# LED_driver.net
KiCad netlist of a schematic drawn in EAGLE
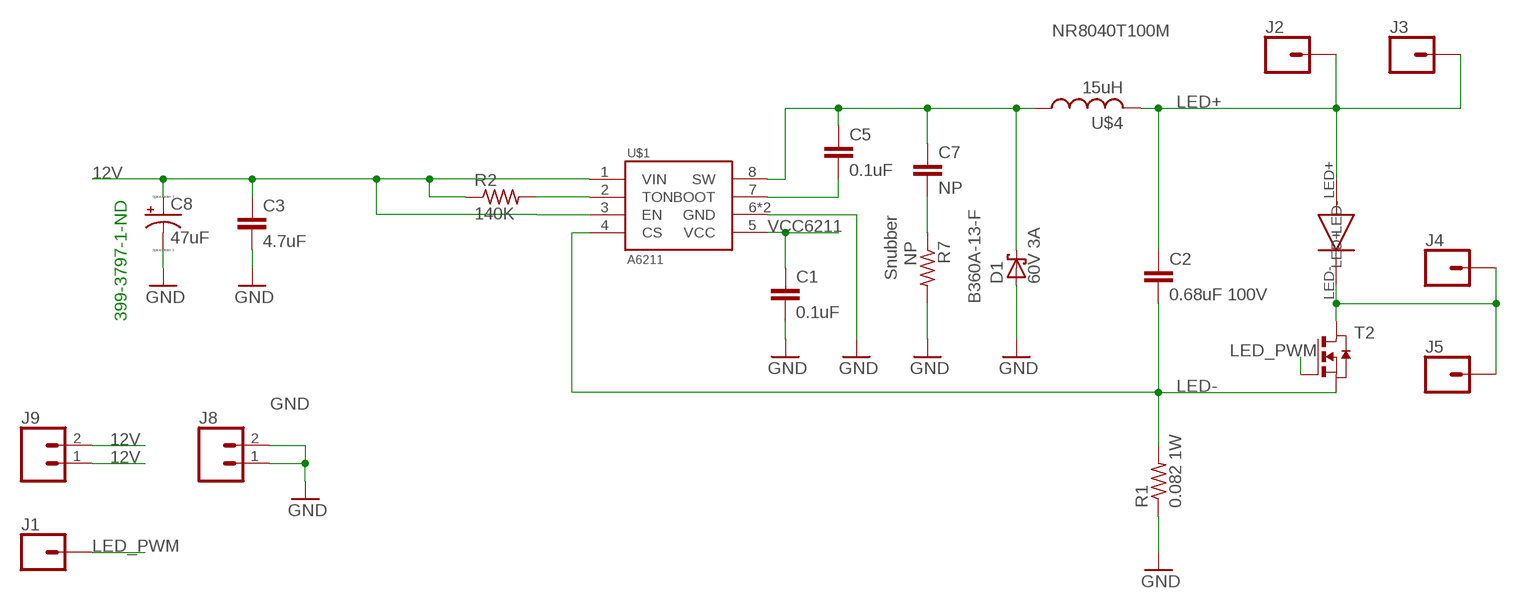
[diagram p0: schematic, sheet 1]

(export (version "E")
  (design (tool "Eeschema 10.0.6"))
  (components
    (comp (ref "C1")
      (value "0.1uF")
      (footprint "eagle-import:C0603")
      (libsource (lib "eagle-import") (part "resistor_C-EUC0603"))
    )
    (comp (ref "C2")
      (value "0.68uF 100V")
      (footprint "eagle-import:C0805")
      (libsource (lib "eagle-import") (part "resistor_C-EUC0805"))
    )
    (comp (ref "C3")
      (value "4.7uF")
      (footprint "eagle-import:C0603")
      (libsource (lib "eagle-import") (part "C-EUC0603"))
    )
    (comp (ref "C5")
      (value "0.1uF")
      (footprint "eagle-import:C0603")
      (libsource (lib "eagle-import") (part "resistor_C-EUC0603"))
    )
    (comp (ref "C7")
      (value "NP")
      (footprint "eagle-import:C0603")
      (libsource (lib "eagle-import") (part "resistor_C-EUC0603"))
    )
    (comp (ref "C8")
      (value "47uF")
      (footprint "eagle-import:CTAN(7.30_4.30MM)")
      (libsource (lib "eagle-import") (part "C-TANTALUM(10UF_150UF)"))
    )
    (comp (ref "D1")
      (value "60V 3A")
      (footprint "eagle-import:SMA")
      (libsource (lib "eagle-import") (part "DIODE-SCHOTTKYSMA"))
    )
    (comp (ref "J1")
      (value "CONN_01")
      (footprint "eagle-import:1X01")
      (libsource (lib "eagle-import") (part "CONN_01"))
    )
    (comp (ref "J2")
      (value "CONN_01")
      (footprint "eagle-import:1X01")
      (libsource (lib "eagle-import") (part "CONN_01"))
    )
    (comp (ref "J3")
      (value "CONN_01")
      (footprint "eagle-import:1X01")
      (libsource (lib "eagle-import") (part "CONN_01"))
    )
    (comp (ref "J4")
      (value "CONN_01")
      (footprint "eagle-import:1X01")
      (libsource (lib "eagle-import") (part "CONN_01"))
    )
    (comp (ref "J5")
      (value "CONN_01")
      (footprint "eagle-import:1X01")
      (libsource (lib "eagle-import") (part "CONN_01"))
    )
    (comp (ref "J8")
      (value "CONN_021X02_NO_SILK")
      (footprint "eagle-import:1X02_NO_SILK")
      (libsource (lib "eagle-import") (part "CONN_021X02_NO_SILK"))
    )
    (comp (ref "J9")
      (value "CONN_021X02_NO_SILK")
      (footprint "eagle-import:1X02_NO_SILK")
      (libsource (lib "eagle-import") (part "CONN_021X02_NO_SILK"))
    )
    (comp (ref "R1")
      (value "0.082 1W")
      (footprint "eagle-import:R2512")
      (libsource (lib "eagle-import") (part "R-US_R2512"))
    )
    (comp (ref "R2")
      (value "140K")
      (footprint "eagle-import:R0603")
      (libsource (lib "eagle-import") (part "R-US_R0603"))
    )
    (comp (ref "R7")
      (value "NP")
      (footprint "eagle-import:R1206")
      (libsource (lib "eagle-import") (part "R-US_R1206"))
    )
    (comp (ref "T2")
      (value "NMOSSOT23")
      (footprint "eagle-import:SOT-23")
      (libsource (lib "eagle-import") (part "NMOSSOT23"))
    )
    (comp (ref "U$1")
      (value "A6211")
      (footprint "eagle-import:SOIC8N-LJ")
      (libsource (lib "eagle-import") (part "A6211"))
    )
    (comp (ref "U$3")
      (value "LED_00H53")
      (footprint "eagle-import:LED_00H53")
      (libsource (lib "eagle-import") (part "LED_00H53"))
    )
    (comp (ref "U$4")
      (value "15uH")
      (footprint "eagle-import:HCMA1305")
      (libsource (lib "eagle-import") (part "HCMA1305"))
    )
  )
  (nets
    (net (code "1") (name "/12V") (class "Default")
      (node (ref "C3") (pin "1") (pinfunction "1_1") (pintype "passive"))
      (node (ref "C8") (pin "+") (pinfunction "+_+") (pintype "passive"))
      (node (ref "J9") (pin "1") (pinfunction "1_1") (pintype "passive"))
      (node (ref "J9") (pin "2") (pinfunction "2_2") (pintype "passive"))
      (node (ref "R2") (pin "1") (pinfunction "1_1") (pintype "passive"))
      (node (ref "U$1") (pin "1") (pinfunction "VIN_1") (pintype "bidirectional"))
      (node (ref "U$1") (pin "3") (pinfunction "EN_3") (pintype "bidirectional"))
    )
    (net (code "2") (name "/LED+") (class "Default")
      (node (ref "C2") (pin "1") (pinfunction "1_1") (pintype "passive"))
      (node (ref "J2") (pin "1") (pinfunction "1_1") (pintype "passive"))
      (node (ref "J3") (pin "1") (pinfunction "1_1") (pintype "passive"))
      (node (ref "U$3") (pin "LED+") (pinfunction "LED+_LED+") (pintype "bidirectional"))
      (node (ref "U$4") (pin "P$2") (pinfunction "2_P$2") (pintype "passive"))
    )
    (net (code "3") (name "/LED-") (class "Default")
      (node (ref "C2") (pin "2") (pinfunction "2_2") (pintype "passive"))
      (node (ref "R1") (pin "2") (pinfunction "2_2") (pintype "passive"))
      (node (ref "T2") (pin "2") (pinfunction "S_2") (pintype "passive"))
      (node (ref "U$1") (pin "4") (pinfunction "CS_4") (pintype "bidirectional"))
    )
    (net (code "4") (name "/LED_PWM") (class "Default")
      (node (ref "J1") (pin "1") (pinfunction "1_1") (pintype "passive"))
      (node (ref "T2") (pin "3") (pinfunction "G_3") (pintype "passive"))
    )
    (net (code "5") (name "/VCC6211") (class "Default")
      (node (ref "C1") (pin "1") (pinfunction "1_1") (pintype "passive"))
      (node (ref "U$1") (pin "5") (pinfunction "VCC_5") (pintype "bidirectional"))
    )
    (net (code "6") (name "GND") (class "Default")
      (node (ref "C1") (pin "2") (pinfunction "2_2") (pintype "passive"))
      (node (ref "C3") (pin "2") (pinfunction "2_2") (pintype "passive"))
      (node (ref "C8") (pin "-") (pinfunction "-_-") (pintype "passive"))
      (node (ref "D1") (pin "A") (pinfunction "A_A") (pintype "passive"))
      (node (ref "J8") (pin "1") (pinfunction "1_1") (pintype "passive"))
      (node (ref "J8") (pin "2") (pinfunction "2_2") (pintype "passive"))
      (node (ref "R1") (pin "1") (pinfunction "1_1") (pintype "passive"))
      (node (ref "R7") (pin "2") (pinfunction "2_2") (pintype "passive"))
      (node (ref "U$1") (pin "6") (pinfunction "GND_6") (pintype "bidirectional"))
      (node (ref "U$1") (pin "PAD") (pinfunction "GND_PAD") (pintype "bidirectional"))
    )
    (net (code "7") (name "Net-(C7-Pad2)") (class "Default")
      (node (ref "C7") (pin "2") (pinfunction "2_2") (pintype "passive"))
      (node (ref "R7") (pin "1") (pinfunction "1_1") (pintype "passive"))
    )
    (net (code "8") (name "Net-(T2-D)") (class "Default")
      (node (ref "J4") (pin "1") (pinfunction "1_1") (pintype "passive"))
      (node (ref "J5") (pin "1") (pinfunction "1_1") (pintype "passive"))
      (node (ref "T2") (pin "1") (pinfunction "D_1") (pintype "passive"))
      (node (ref "U$3") (pin "LED-") (pinfunction "LED-_LED-") (pintype "bidirectional"))
    )
    (net (code "9") (name "Net-(U$1-BOOT)") (class "Default")
      (node (ref "C5") (pin "2") (pinfunction "2_2") (pintype "passive"))
      (node (ref "U$1") (pin "7") (pinfunction "BOOT_7") (pintype "bidirectional"))
    )
    (net (code "10") (name "Net-(U$1-SW)") (class "Default")
      (node (ref "C5") (pin "1") (pinfunction "1_1") (pintype "passive"))
      (node (ref "C7") (pin "1") (pinfunction "1_1") (pintype "passive"))
      (node (ref "D1") (pin "C") (pinfunction "C_C") (pintype "passive"))
      (node (ref "U$1") (pin "8") (pinfunction "SW_8") (pintype "bidirectional"))
      (node (ref "U$4") (pin "P$1") (pinfunction "1_P$1") (pintype "passive"))
    )
    (net (code "11") (name "Net-(U$1-TON)") (class "Default")
      (node (ref "R2") (pin "2") (pinfunction "2_2") (pintype "passive"))
      (node (ref "U$1") (pin "2") (pinfunction "TON_2") (pintype "bidirectional"))
    )
  )
)
